# SPI_Extender_1.net
KiCad netlist of a schematic drawn in Altium Designer
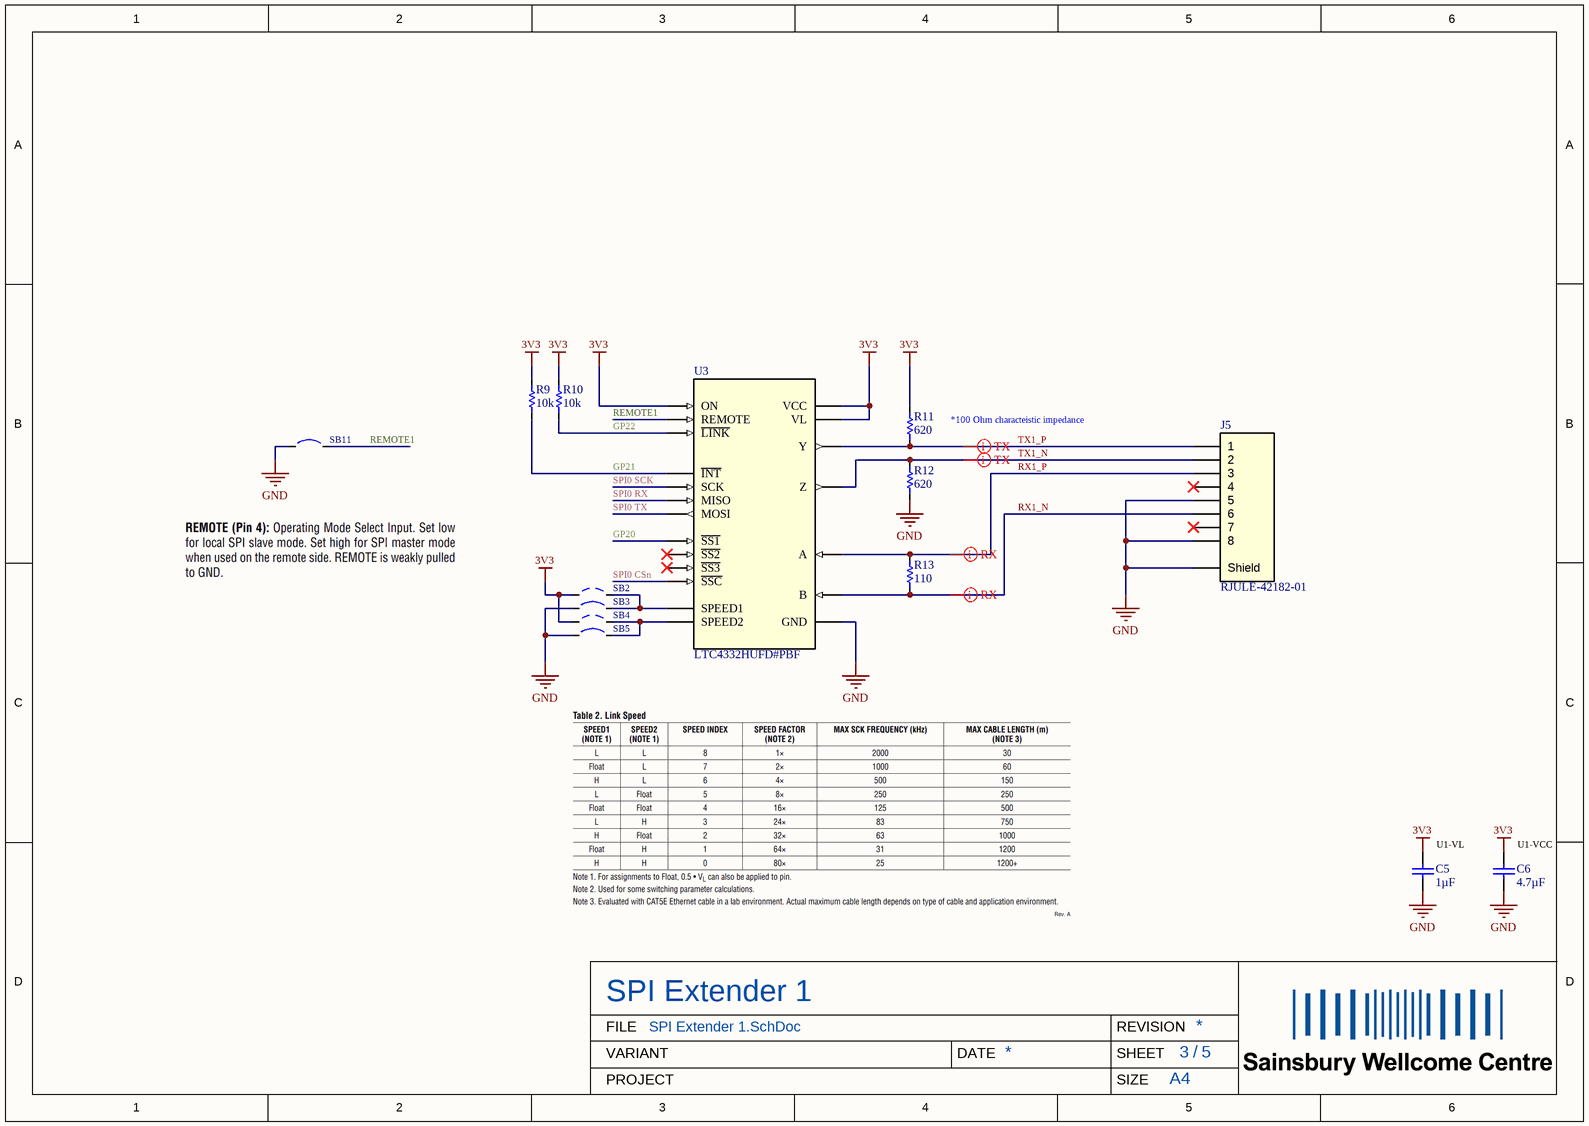
[diagram p0: SPI Extender 1.SchDoc]

(export (version "E")
  (design (tool "Eeschema 10.0.6"))
  (components
    (comp (ref "C5")
      (value "1µF")
      (footprint "FP-GRM188-0_1-e0_2_0_5-IPC_B")
      (description "1µF ±10% 25V Ceramic Capacitor X7R 0603 (1608 Metric)")
      (fields (field (name "VOLTAGE") "25V") (field (name "TOLERANCE") "10%"))
      (libsource (lib "Sainsbury Wellcome Centre") (part "Cap"))
    )
    (comp (ref "C6")
      (value "4.7µF")
      (footprint "CAPC2012X88N")
      (description "4.7uF ±5% 16V Ceramic Capacitor X7R 0805 (2012 Metric)")
      (fields (field (name "TOLERANCE") "5%") (field (name "VOLTAGE") "16V"))
      (libsource (lib "Sainsbury Wellcome Centre") (part "Cap"))
    )
    (comp (ref "J5")
      (value "RJULE4218201")
      (footprint "RJULE-42182-01 - RM")
      (description "Modular Jack - Right Angle, Input Output Connectors RJ45, 8P8C, Without LEDs, Shield.")
      (fields (field (name "PARTNUMBER") "RJULE-42182-01"))
      (libsource (lib "Sainsbury Wellcome Centre") (part "RJULE-42182-01"))
    )
    (comp (ref "R9")
      (value "10k")
      (footprint "FP-CPF0603-IPC_B")
      (description "Surface Mount Resistor 10k Ohm 1/16 W 0.1% 0603 (1608 Metric)")
      (fields (field (name "TOLERANCE") "0.1%") (field (name "Comment") "R0603-10k-1/16W-0.1%"))
      (libsource (lib "Sainsbury Wellcome Centre") (part "Res"))
    )
    (comp (ref "R10")
      (value "10k")
      (footprint "FP-CPF0603-IPC_B")
      (description "Surface Mount Resistor 10k Ohm 1/16 W 0.1% 0603 (1608 Metric)")
      (fields (field (name "TOLERANCE") "0.1%") (field (name "Comment") "R0603-10k-1/16W-0.1%"))
      (libsource (lib "Sainsbury Wellcome Centre") (part "Res"))
    )
    (comp (ref "R11")
      (value "620")
      (footprint "FP-CPF0603-IPC_B")
      (description "Surface Mount Resistor 620 Ohm 1/16 W 0.1% 0603 (1608 Metric)")
      (fields (field (name "TOLERANCE") "0.1%") (field (name "Comment") "R0603-620R-1/16W-0.1%"))
      (libsource (lib "Sainsbury Wellcome Centre") (part "Res"))
    )
    (comp (ref "R12")
      (value "620")
      (footprint "FP-CPF0603-IPC_B")
      (description "Surface Mount Resistor 620 Ohm 1/16 W 0.1% 0603 (1608 Metric)")
      (fields (field (name "TOLERANCE") "0.1%") (field (name "Comment") "R0603-620R-1/16W-0.1%"))
      (libsource (lib "Sainsbury Wellcome Centre") (part "Res"))
    )
    (comp (ref "R13")
      (value "110")
      (footprint "FP-CPF0603-IPC_B")
      (description "Surface Mount Resistor 110 Ohm 1/16 W 0.1% 0603 (1608 Metric)")
      (fields (field (name "TOLERANCE") "0.1%") (field (name "Comment") "R0603-110R-1/16W-0.1%"))
      (libsource (lib "Sainsbury Wellcome Centre") (part "Res"))
    )
    (comp (ref "SB2")
      (value "Solder Bridge 0603 Off")
      (footprint "Solder Bridge 0603 Off")
      (description "Solder Bridge 0603 OFF")
      (libsource (lib "Sainsbury Wellcome Centre") (part "Solder Bridge Off"))
    )
    (comp (ref "SB3")
      (value "Solder Bridge 0603 On")
      (footprint "Solder Bridge 0603 On")
      (description "Solder Bridge 0603 ON")
      (fields (field (name "PARTNUMBER") "R0603-0R-1/16W-0.1%"))
      (libsource (lib "Sainsbury Wellcome Centre") (part "Solder Bridge On"))
    )
    (comp (ref "SB4")
      (value "Solder Bridge 0603 Off")
      (footprint "Solder Bridge 0603 Off")
      (description "Solder Bridge 0603 OFF")
      (libsource (lib "Sainsbury Wellcome Centre") (part "Solder Bridge Off"))
    )
    (comp (ref "SB5")
      (value "Solder Bridge 0603 On")
      (footprint "Solder Bridge 0603 On")
      (description "Solder Bridge 0603 ON")
      (fields (field (name "PARTNUMBER") "R0603-0R-1/16W-0.1%"))
      (libsource (lib "Sainsbury Wellcome Centre") (part "Solder Bridge On"))
    )
    (comp (ref "SB11")
      (value "Solder Bridge 0603 On")
      (footprint "Solder Bridge 0603 On")
      (description "Solder Bridge 0603 ON")
      (fields (field (name "PARTNUMBER") "R0603-0R-1/16W-0.1%"))
      (libsource (lib "Sainsbury Wellcome Centre") (part "Solder Bridge On"))
    )
    (comp (ref "U3")
      (value "LTC4332HUFD#PBF")
      (footprint "FP-UFD-20-05-08-1711-IPC_B")
      (description "SPI Extender Over Rugged Differential Link")
      (libsource (lib "Sainsbury Wellcome Centre") (part "LTC4332"))
    )
  )
  (nets
    (net (code "1") (name "/GP20") (class "Default")
      (node (ref "U3") (pin "11") (pinfunction "~{SS1}_11") (pintype "input"))
    )
    (net (code "2") (name "/GP21") (class "Default")
      (node (ref "R9") (pin "1") (pinfunction "1_1") (pintype "passive"))
      (node (ref "U3") (pin "10") (pinfunction "~{INT}_10") (pintype "passive"))
    )
    (net (code "3") (name "/GP22") (class "Default")
      (node (ref "R10") (pin "1") (pinfunction "1_1") (pintype "passive"))
      (node (ref "U3") (pin "5") (pinfunction "~{LINK}_5") (pintype "input"))
    )
    (net (code "4") (name "/REMOTE1") (class "Default")
      (node (ref "SB11") (pin "2") (pinfunction "2_2") (pintype "passive"))
      (node (ref "U3") (pin "4") (pinfunction "REMOTE_4") (pintype "input"))
    )
    (net (code "5") (name "/RX1_N") (class "Default")
      (node (ref "J5") (pin "6") (pinfunction "6_6") (pintype "passive"))
      (node (ref "R13") (pin "1") (pinfunction "1_1") (pintype "passive"))
      (node (ref "U3") (pin "19") (pinfunction "B_19") (pintype "input"))
    )
    (net (code "6") (name "/RX1_P") (class "Default")
      (node (ref "J5") (pin "3") (pinfunction "3_3") (pintype "passive"))
      (node (ref "R13") (pin "2") (pinfunction "2_2") (pintype "passive"))
      (node (ref "U3") (pin "20") (pinfunction "A_20") (pintype "input"))
    )
    (net (code "7") (name "/SPI0 CSn") (class "Default")
      (node (ref "U3") (pin "6") (pinfunction "~{SSC}_6") (pintype "input"))
    )
    (net (code "8") (name "/SPI0 RX") (class "Default")
      (node (ref "U3") (pin "9") (pinfunction "MISO_9") (pintype "input"))
    )
    (net (code "9") (name "/SPI0 SCK") (class "Default")
      (node (ref "U3") (pin "7") (pinfunction "SCK_7") (pintype "input"))
    )
    (net (code "10") (name "/SPI0 TX") (class "Default")
      (node (ref "U3") (pin "8") (pinfunction "MOSI_8") (pintype "output"))
    )
    (net (code "11") (name "/TX1_N") (class "Default")
      (node (ref "J5") (pin "2") (pinfunction "2_2") (pintype "passive"))
      (node (ref "R12") (pin "2") (pinfunction "2_2") (pintype "passive"))
      (node (ref "U3") (pin "18") (pinfunction "Z_18") (pintype "output"))
    )
    (net (code "12") (name "/TX1_P") (class "Default")
      (node (ref "J5") (pin "1") (pinfunction "1_1") (pintype "passive"))
      (node (ref "R11") (pin "1") (pinfunction "1_1") (pintype "passive"))
      (node (ref "U3") (pin "17") (pinfunction "Y_17") (pintype "output"))
    )
    (net (code "13") (name "3V3") (class "Default")
      (node (ref "C5") (pin "2") (pinfunction "2_2") (pintype "passive"))
      (node (ref "C6") (pin "2") (pinfunction "2_2") (pintype "passive"))
      (node (ref "R10") (pin "2") (pinfunction "2_2") (pintype "passive"))
      (node (ref "R11") (pin "2") (pinfunction "2_2") (pintype "passive"))
      (node (ref "R9") (pin "2") (pinfunction "2_2") (pintype "passive"))
      (node (ref "SB2") (pin "1") (pinfunction "1_1") (pintype "passive"))
      (node (ref "SB4") (pin "1") (pinfunction "1_1") (pintype "passive"))
      (node (ref "U3") (pin "1") (pinfunction "VCC_1") (pintype "power_in"))
      (node (ref "U3") (pin "2") (pinfunction "VL_2") (pintype "power_in"))
      (node (ref "U3") (pin "3") (pinfunction "ON_3") (pintype "input"))
    )
    (net (code "14") (name "GND") (class "Default")
      (node (ref "C5") (pin "1") (pinfunction "1_1") (pintype "passive"))
      (node (ref "C6") (pin "1") (pinfunction "1_1") (pintype "passive"))
      (node (ref "J5") (pin "5") (pinfunction "5_5") (pintype "passive"))
      (node (ref "J5") (pin "8") (pinfunction "8_8") (pintype "passive"))
      (node (ref "J5") (pin "MH") (pinfunction "Shield_MH") (pintype "passive"))
      (node (ref "R12") (pin "1") (pinfunction "1_1") (pintype "passive"))
      (node (ref "SB11") (pin "1") (pinfunction "1_1") (pintype "passive"))
      (node (ref "SB3") (pin "1") (pinfunction "1_1") (pintype "passive"))
      (node (ref "SB5") (pin "1") (pinfunction "1_1") (pintype "passive"))
      (node (ref "U3") (pin "16") (pinfunction "GND_16") (pintype "power_in"))
    )
    (net (code "15") (name "Net-(U3-SPEED1)") (class "Default")
      (node (ref "SB2") (pin "2") (pinfunction "2_2") (pintype "passive"))
      (node (ref "SB3") (pin "2") (pinfunction "2_2") (pintype "passive"))
      (node (ref "U3") (pin "14") (pinfunction "SPEED1_14") (pintype "passive"))
    )
    (net (code "16") (name "Net-(U3-SPEED2)") (class "Default")
      (node (ref "SB4") (pin "2") (pinfunction "2_2") (pintype "passive"))
      (node (ref "SB5") (pin "2") (pinfunction "2_2") (pintype "passive"))
      (node (ref "U3") (pin "15") (pinfunction "SPEED2_15") (pintype "passive"))
    )
    (net (code "17") (name "unconnected-(J5-Pad4)") (class "Default")
      (node (ref "J5") (pin "4") (pinfunction "4_4") (pintype "passive+no_connect"))
    )
    (net (code "18") (name "unconnected-(J5-Pad7)") (class "Default")
      (node (ref "J5") (pin "7") (pinfunction "7_7") (pintype "passive+no_connect"))
    )
    (net (code "19") (name "unconnected-(U3-~{SS2}-Pad12)") (class "Default")
      (node (ref "U3") (pin "12") (pinfunction "~{SS2}_12") (pintype "input+no_connect"))
    )
    (net (code "20") (name "unconnected-(U3-~{SS3}-Pad13)") (class "Default")
      (node (ref "U3") (pin "13") (pinfunction "~{SS3}_13") (pintype "input+no_connect"))
    )
  )
)
